# Microcontroller.net
KiCad netlist of a schematic drawn in Altium Designer
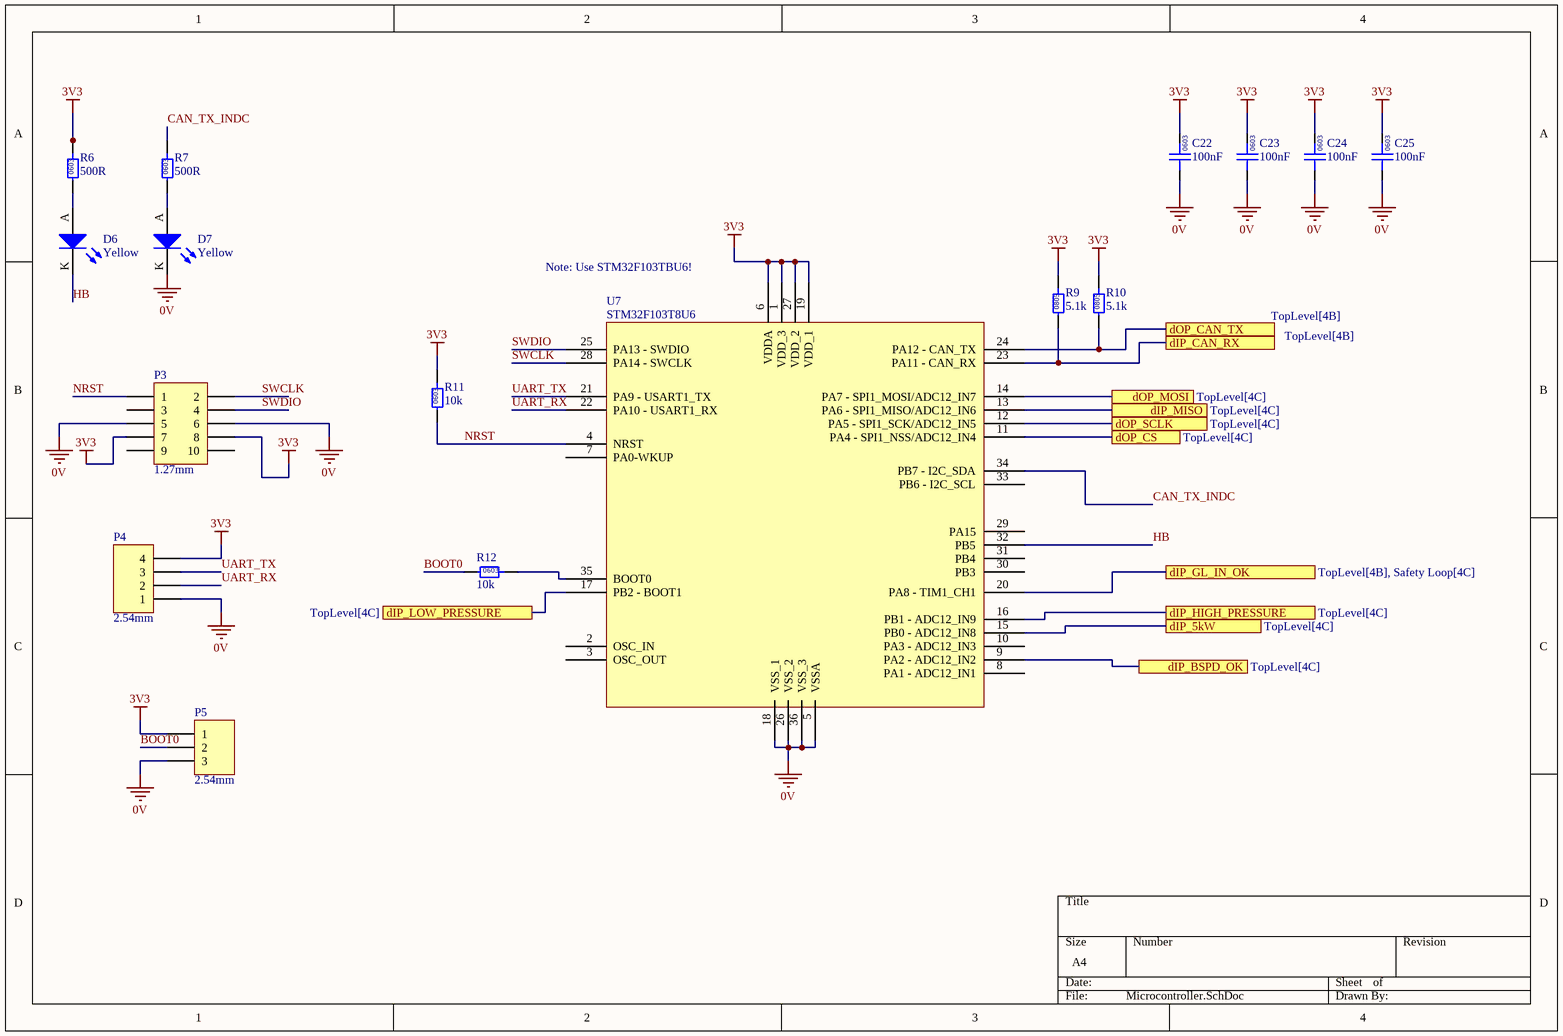
[diagram p0: Microcontroller.SchDoc]

(export (version "E")
  (design (tool "Eeschema 10.0.6"))
  (components
    (comp (ref "C22")
      (value "100nF")
      (footprint "0603")
      (fields
        (field (name "PART NUMBER") "GCM188L81H104KA57D")
        (field (name "MANUFACTURER") "muRata")
        (field (name "TOLERANCE") "±10%")
      )
      (libsource (lib "ts_standard_library") (part "Capacitor 0603"))
    )
    (comp (ref "C23")
      (value "100nF")
      (footprint "0603")
      (fields
        (field (name "PART NUMBER") "GCM188L81H104KA57D")
        (field (name "MANUFACTURER") "muRata")
        (field (name "TOLERANCE") "±10%")
      )
      (libsource (lib "ts_standard_library") (part "Capacitor 0603"))
    )
    (comp (ref "C24")
      (value "100nF")
      (footprint "0603")
      (fields
        (field (name "PART NUMBER") "GCM188L81H104KA57D")
        (field (name "MANUFACTURER") "muRata")
        (field (name "TOLERANCE") "±10%")
      )
      (libsource (lib "ts_standard_library") (part "Capacitor 0603"))
    )
    (comp (ref "C25")
      (value "100nF")
      (footprint "0603")
      (fields
        (field (name "PART NUMBER") "GCM188L81H104KA57D")
        (field (name "MANUFACTURER") "muRata")
        (field (name "TOLERANCE") "±10%")
      )
      (libsource (lib "ts_standard_library") (part "Capacitor 0603"))
    )
    (comp (ref "D6")
      (value "Yellow")
      (footprint "0805 LED")
      (description "Yellow LED Indication - Discrete 1.75V 0805 (2012 Metric)")
      (fields (field (name "PART NUMBER") "SML-211YTT86") (field (name "MANUFACTURER") "ROHM Semiconductor"))
      (libsource (lib "ts_standard_library") (part "LED"))
    )
    (comp (ref "D7")
      (value "Yellow")
      (footprint "0805 LED")
      (description "Yellow LED Indication - Discrete 1.75V 0805 (2012 Metric)")
      (fields (field (name "PART NUMBER") "SML-211YTT86") (field (name "MANUFACTURER") "ROHM Semiconductor"))
      (libsource (lib "ts_standard_library") (part "LED"))
    )
    (comp (ref "P3")
      (value "1.27mm")
      (footprint "3221-10-0300-00")
      (fields
        (field (name "PART NUMBER") "SMD 1.27mm Header 2x5 (3221-10-0300-00)")
        (field (name "CONTACT") "NA")
      )
      (libsource (lib "ts_standard_connectors") (part "Header 2x5"))
    )
    (comp (ref "P4")
      (value "2.54mm")
      (footprint "TH 2.54mm Header 1x4")
      (fields (field (name "PART NUMBER") "TH 2.54mm Header 1x4") (field (name "CONTACT") "NA"))
      (libsource (lib "ts_standard_connectors") (part "Header 1x4"))
    )
    (comp (ref "P5")
      (value "2.54mm")
      (footprint "TH 2.54mm Header 1x3")
      (fields (field (name "PART NUMBER") "TH 2.54mm Header 1x3") (field (name "CONTACT") "NA"))
      (libsource (lib "ts_standard_connectors") (part "Header 1x3"))
    )
    (comp (ref "R6")
      (value "500R")
      (footprint "0603")
      (fields
        (field (name "PART NUMBER") "RT0603BRD07500RL")
        (field (name "MANUFACTURER") "YAGEO")
        (field (name "TOLERANCE") "0.01")
      )
      (libsource (lib "ts_standard_library") (part "Resistor 0603"))
    )
    (comp (ref "R7")
      (value "500R")
      (footprint "0603")
      (fields
        (field (name "PART NUMBER") "RT0603BRD07500RL")
        (field (name "MANUFACTURER") "YAGEO")
        (field (name "TOLERANCE") "0.01")
      )
      (libsource (lib "ts_standard_library") (part "Resistor 0603"))
    )
    (comp (ref "R9")
      (value "5.1k")
      (footprint "0805")
      (fields
        (field (name "PART NUMBER") "RC0805FR075K1L")
        (field (name "MANUFACTURER") "YAGEO")
        (field (name "TOLERANCE") "0.01")
      )
      (libsource (lib "ts_standard_library") (part "Resistor 0805"))
    )
    (comp (ref "R10")
      (value "5.1k")
      (footprint "0805")
      (fields
        (field (name "PART NUMBER") "RC0805FR075K1L")
        (field (name "MANUFACTURER") "YAGEO")
        (field (name "TOLERANCE") "0.01")
      )
      (libsource (lib "ts_standard_library") (part "Resistor 0805"))
    )
    (comp (ref "R11")
      (value "10k")
      (footprint "0603")
      (fields
        (field (name "PART NUMBER") "RC0603FR-0710KL")
        (field (name "MANUFACTURER") "YAGEO")
        (field (name "TOLERANCE") "0.01")
      )
      (libsource (lib "ts_standard_library") (part "Resistor 0603"))
    )
    (comp (ref "R12")
      (value "10k")
      (footprint "0603")
      (fields
        (field (name "PART NUMBER") "RC0603FR-0710KL")
        (field (name "MANUFACTURER") "YAGEO")
        (field (name "TOLERANCE") "0.01")
      )
      (libsource (lib "ts_standard_library") (part "Resistor 0603"))
    )
    (comp (ref "U7")
      (value "STM32F103T8U6")
      (footprint "STM_QFN-36")
      (description "ARM® Cortex®-M3 STM32F1 Microcontroller IC 32-Bit 72MHz 64KB (64K x 8) FLASH QFN")
      (fields (field (name "MANUFACTURER") "ST Microelectronics"))
      (libsource (lib "ts_standard_library") (part "STM32F103T8U6"))
    )
  )
  (nets
    (net (code "1") (name "/BOOT0") (class "Default")
      (node (ref "P5") (pin "2") (pinfunction "2_2") (pintype "passive"))
      (node (ref "R12") (pin "1") (pinfunction "1_1") (pintype "passive"))
    )
    (net (code "2") (name "/CAN_TX_INDC") (class "Default")
      (node (ref "R7") (pin "2") (pinfunction "2_2") (pintype "passive"))
      (node (ref "U7") (pin "34") (pinfunction "PB7_-_I2C_SDA_34") (pintype "passive"))
    )
    (net (code "3") (name "/HB") (class "Default")
      (node (ref "D6") (pin "K") (pinfunction "K_K") (pintype "passive"))
      (node (ref "U7") (pin "32") (pinfunction "PB5_32") (pintype "passive"))
    )
    (net (code "4") (name "/NRST") (class "Default")
      (node (ref "P3") (pin "1") (pinfunction "1_1") (pintype "passive"))
      (node (ref "R11") (pin "1") (pinfunction "1_1") (pintype "passive"))
      (node (ref "U7") (pin "4") (pinfunction "NRST_4") (pintype "passive"))
    )
    (net (code "5") (name "/SWCLK") (class "Default")
      (node (ref "P3") (pin "2") (pinfunction "2_2") (pintype "passive"))
      (node (ref "U7") (pin "28") (pinfunction "PA14_-_SWCLK_28") (pintype "passive"))
    )
    (net (code "6") (name "/SWDIO") (class "Default")
      (node (ref "P3") (pin "4") (pinfunction "4_4") (pintype "passive"))
      (node (ref "U7") (pin "25") (pinfunction "PA13_-_SWDIO_25") (pintype "passive"))
    )
    (net (code "7") (name "/UART_RX") (class "Default")
      (node (ref "P4") (pin "2") (pinfunction "2_2") (pintype "passive"))
      (node (ref "U7") (pin "22") (pinfunction "PA10_-_USART1_RX_22") (pintype "passive"))
    )
    (net (code "8") (name "/UART_TX") (class "Default")
      (node (ref "P4") (pin "3") (pinfunction "3_3") (pintype "passive"))
      (node (ref "U7") (pin "21") (pinfunction "PA9_-_USART1_TX_21") (pintype "passive"))
    )
    (net (code "9") (name "/dIP_5kW") (class "Default")
      (node (ref "U7") (pin "15") (pinfunction "PB0_-_ADC12_IN8_15") (pintype "passive"))
    )
    (net (code "10") (name "/dIP_BSPD_OK") (class "Default")
      (node (ref "U7") (pin "9") (pinfunction "PA2_-_ADC12_IN2_9") (pintype "passive"))
    )
    (net (code "11") (name "/dIP_CAN_RX") (class "Default")
      (node (ref "R9") (pin "1") (pinfunction "1_1") (pintype "passive"))
      (node (ref "U7") (pin "23") (pinfunction "PA11_-_CAN_RX_23") (pintype "passive"))
    )
    (net (code "12") (name "/dIP_GL_IN_OK") (class "Default")
      (node (ref "U7") (pin "20") (pinfunction "PA8_-_TIM1_CH1_20") (pintype "passive"))
    )
    (net (code "13") (name "/dIP_HIGH_PRESSURE") (class "Default")
      (node (ref "U7") (pin "16") (pinfunction "PB1_-_ADC12_IN9_16") (pintype "passive"))
    )
    (net (code "14") (name "/dIP_LOW_PRESSURE") (class "Default")
      (node (ref "U7") (pin "17") (pinfunction "PB2_-_BOOT1_17") (pintype "passive"))
    )
    (net (code "15") (name "/dIP_MISO") (class "Default")
      (node (ref "U7") (pin "13") (pinfunction "PA6_-_SPI1_MISO/ADC12_IN6_13") (pintype "passive"))
    )
    (net (code "16") (name "/dOP_CAN_TX") (class "Default")
      (node (ref "R10") (pin "1") (pinfunction "1_1") (pintype "passive"))
      (node (ref "U7") (pin "24") (pinfunction "PA12_-_CAN_TX_24") (pintype "passive"))
    )
    (net (code "17") (name "/dOP_CS") (class "Default")
      (node (ref "U7") (pin "11") (pinfunction "PA4_-_SPI1_NSS/ADC12_IN4_11") (pintype "passive"))
    )
    (net (code "18") (name "/dOP_MOSI") (class "Default")
      (node (ref "U7") (pin "14") (pinfunction "PA7_-_SPI1_MOSI/ADC12_IN7_14") (pintype "passive"))
    )
    (net (code "19") (name "/dOP_SCLK") (class "Default")
      (node (ref "U7") (pin "12") (pinfunction "PA5_-_SPI1_SCK/ADC12_IN5_12") (pintype "passive"))
    )
    (net (code "20") (name "0V") (class "Default")
      (node (ref "C22") (pin "1") (pinfunction "1_1") (pintype "passive"))
      (node (ref "C23") (pin "1") (pinfunction "1_1") (pintype "passive"))
      (node (ref "C24") (pin "1") (pinfunction "1_1") (pintype "passive"))
      (node (ref "C25") (pin "1") (pinfunction "1_1") (pintype "passive"))
      (node (ref "D7") (pin "K") (pinfunction "K_K") (pintype "passive"))
      (node (ref "P3") (pin "5") (pinfunction "5_5") (pintype "passive"))
      (node (ref "P3") (pin "6") (pinfunction "6_6") (pintype "passive"))
      (node (ref "P4") (pin "1") (pinfunction "1_1") (pintype "passive"))
      (node (ref "P5") (pin "3") (pinfunction "3_3") (pintype "passive"))
      (node (ref "U7") (pin "18") (pinfunction "VSS_1_18") (pintype "passive"))
      (node (ref "U7") (pin "26") (pinfunction "VSS_2_26") (pintype "passive"))
      (node (ref "U7") (pin "36") (pinfunction "VSS_3_36") (pintype "passive"))
      (node (ref "U7") (pin "5") (pinfunction "VSSA_5") (pintype "passive"))
    )
    (net (code "21") (name "3V3") (class "Default")
      (node (ref "C22") (pin "2") (pinfunction "2_2") (pintype "passive"))
      (node (ref "C23") (pin "2") (pinfunction "2_2") (pintype "passive"))
      (node (ref "C24") (pin "2") (pinfunction "2_2") (pintype "passive"))
      (node (ref "C25") (pin "2") (pinfunction "2_2") (pintype "passive"))
      (node (ref "P3") (pin "7") (pinfunction "7_7") (pintype "passive"))
      (node (ref "P3") (pin "8") (pinfunction "8_8") (pintype "passive"))
      (node (ref "P4") (pin "4") (pinfunction "4_4") (pintype "passive"))
      (node (ref "P5") (pin "1") (pinfunction "1_1") (pintype "passive"))
      (node (ref "R10") (pin "2") (pinfunction "2_2") (pintype "passive"))
      (node (ref "R11") (pin "2") (pinfunction "2_2") (pintype "passive"))
      (node (ref "R6") (pin "2") (pinfunction "2_2") (pintype "passive"))
      (node (ref "R9") (pin "2") (pinfunction "2_2") (pintype "passive"))
      (node (ref "U7") (pin "1") (pinfunction "VDD_3_1") (pintype "passive"))
      (node (ref "U7") (pin "19") (pinfunction "VDD_1_19") (pintype "passive"))
      (node (ref "U7") (pin "27") (pinfunction "VDD_2_27") (pintype "passive"))
      (node (ref "U7") (pin "6") (pinfunction "VDDA_6") (pintype "passive"))
    )
    (net (code "22") (name "Net-(D6-PadA)") (class "Default")
      (node (ref "D6") (pin "A") (pinfunction "A_A") (pintype "passive"))
      (node (ref "R6") (pin "1") (pinfunction "1_1") (pintype "passive"))
    )
    (net (code "23") (name "Net-(D7-PadA)") (class "Default")
      (node (ref "D7") (pin "A") (pinfunction "A_A") (pintype "passive"))
      (node (ref "R7") (pin "1") (pinfunction "1_1") (pintype "passive"))
    )
    (net (code "24") (name "Net-(U7-BOOT0)") (class "Default")
      (node (ref "R12") (pin "2") (pinfunction "2_2") (pintype "passive"))
      (node (ref "U7") (pin "35") (pinfunction "BOOT0_35") (pintype "passive"))
    )
    (net (code "25") (name "unconnected-(P3-Pad3)") (class "Default")
      (node (ref "P3") (pin "3") (pinfunction "3_3") (pintype "passive"))
    )
    (net (code "26") (name "unconnected-(P3-Pad9)") (class "Default")
      (node (ref "P3") (pin "9") (pinfunction "9_9") (pintype "passive"))
    )
    (net (code "27") (name "unconnected-(P3-Pad10)") (class "Default")
      (node (ref "P3") (pin "10") (pinfunction "10_10") (pintype "passive"))
    )
    (net (code "28") (name "unconnected-(U7-OSC_IN-Pad2)") (class "Default")
      (node (ref "U7") (pin "2") (pinfunction "OSC_IN_2") (pintype "passive"))
    )
    (net (code "29") (name "unconnected-(U7-OSC_OUT-Pad3)") (class "Default")
      (node (ref "U7") (pin "3") (pinfunction "OSC_OUT_3") (pintype "passive"))
    )
    (net (code "30") (name "unconnected-(U7-PA0-WKUP-Pad7)") (class "Default")
      (node (ref "U7") (pin "7") (pinfunction "PA0-WKUP_7") (pintype "passive"))
    )
    (net (code "31") (name "unconnected-(U7-PA1_-_ADC12_IN1-Pad8)") (class "Default")
      (node (ref "U7") (pin "8") (pinfunction "PA1_-_ADC12_IN1_8") (pintype "passive"))
    )
    (net (code "32") (name "unconnected-(U7-PA3_-_ADC12_IN3-Pad10)") (class "Default")
      (node (ref "U7") (pin "10") (pinfunction "PA3_-_ADC12_IN3_10") (pintype "passive"))
    )
    (net (code "33") (name "unconnected-(U7-PA15-Pad29)") (class "Default")
      (node (ref "U7") (pin "29") (pinfunction "PA15_29") (pintype "passive"))
    )
    (net (code "34") (name "unconnected-(U7-PB3-Pad30)") (class "Default")
      (node (ref "U7") (pin "30") (pinfunction "PB3_30") (pintype "passive"))
    )
    (net (code "35") (name "unconnected-(U7-PB4-Pad31)") (class "Default")
      (node (ref "U7") (pin "31") (pinfunction "PB4_31") (pintype "passive"))
    )
    (net (code "36") (name "unconnected-(U7-PB6_-_I2C_SCL-Pad33)") (class "Default")
      (node (ref "U7") (pin "33") (pinfunction "PB6_-_I2C_SCL_33") (pintype "passive"))
    )
  )
)
